# KeeWatch_LCD.net
KiCad netlist of a schematic drawn in Altium Designer
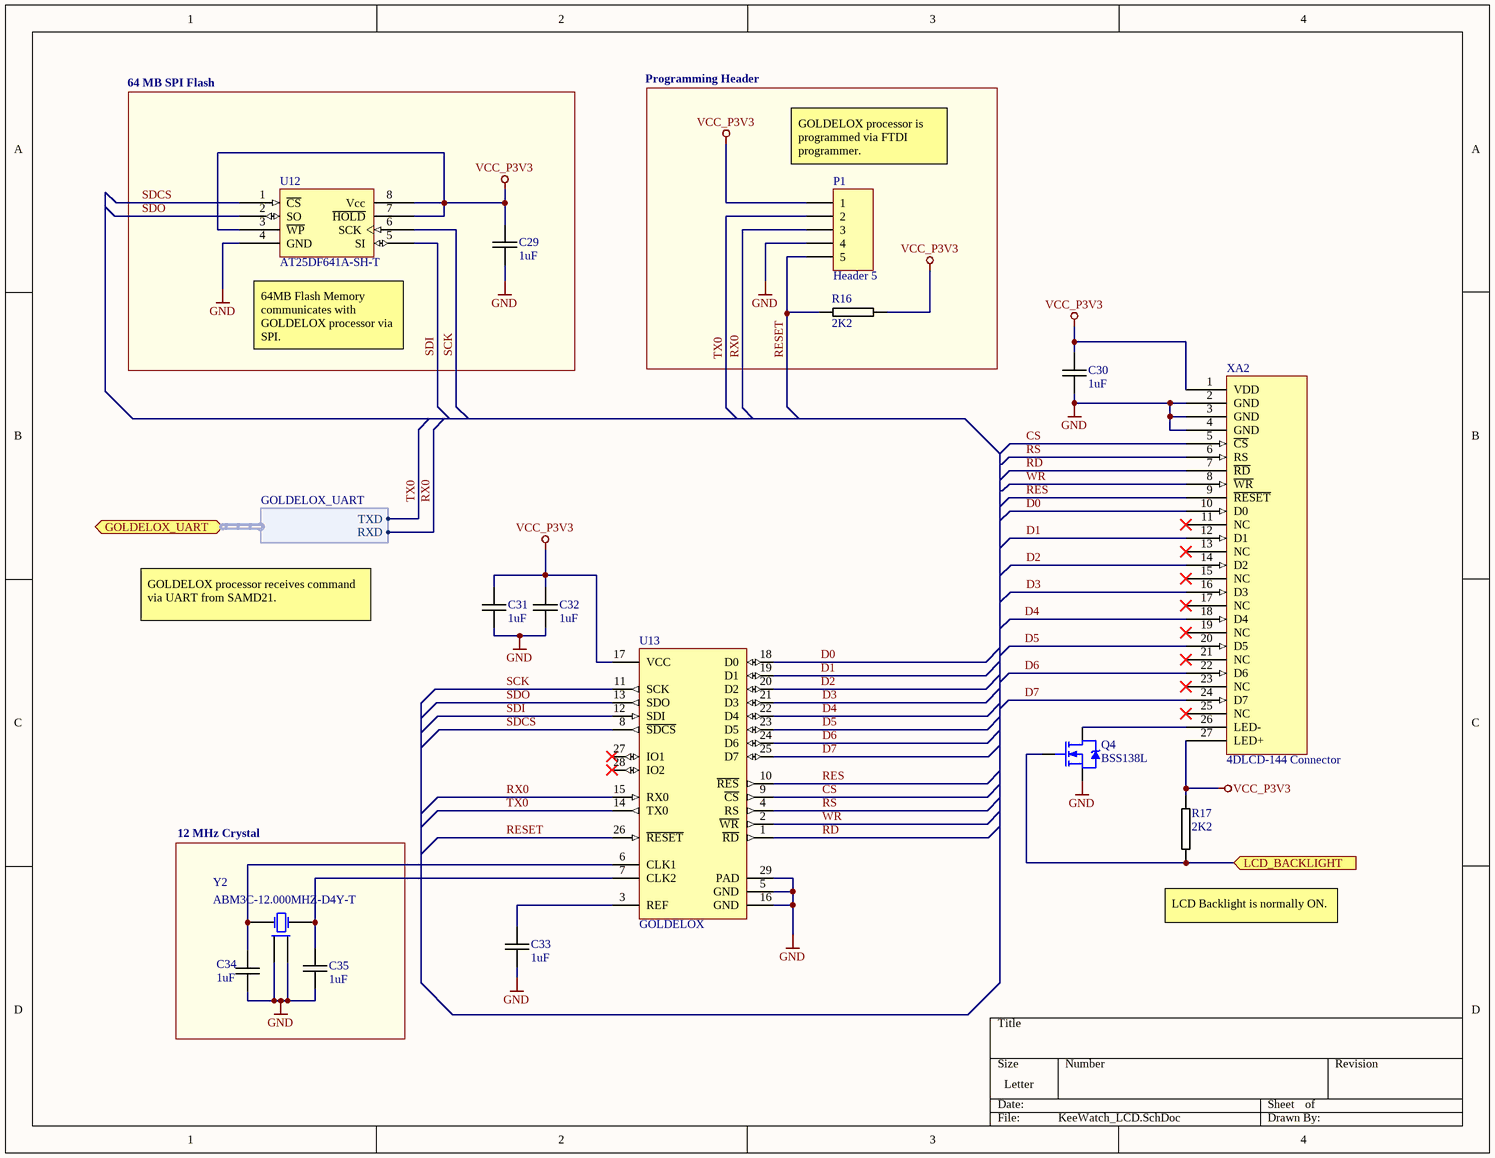
[diagram p0: KeeWatch_LCD.SchDoc]

(export (version "E")
  (design (tool "Eeschema 10.0.6"))
  (components
    (comp (ref "C29")
      (value "1uF")
      (footprint "0603-Cap")
      (description "CAPACITOR 0603 CERAMIC")
      (libsource (lib "Passives") (part "0603-Cap"))
    )
    (comp (ref "C30")
      (value "1uF")
      (footprint "0603-Cap")
      (description "CAPACITOR 0603 CERAMIC")
      (libsource (lib "Passives") (part "0603-Cap"))
    )
    (comp (ref "C31")
      (value "1uF")
      (footprint "0603-Cap")
      (description "CAPACITOR 0603 CERAMIC")
      (libsource (lib "Passives") (part "0603-Cap"))
    )
    (comp (ref "C32")
      (value "1uF")
      (footprint "0603-Cap")
      (description "CAPACITOR 0603 CERAMIC")
      (libsource (lib "Passives") (part "0603-Cap"))
    )
    (comp (ref "C33")
      (value "1uF")
      (footprint "0603-Cap")
      (description "CAPACITOR 0603 CERAMIC")
      (libsource (lib "Passives") (part "0603-Cap"))
    )
    (comp (ref "C34")
      (value "1uF")
      (footprint "0603-Cap")
      (description "CAPACITOR 0603 CERAMIC")
      (libsource (lib "Passives") (part "0603-Cap"))
    )
    (comp (ref "C35")
      (value "1uF")
      (footprint "0603-Cap")
      (description "CAPACITOR 0603 CERAMIC")
      (libsource (lib "Passives") (part "0603-Cap"))
    )
    (comp (ref "P1")
      (value "Header 5")
      (footprint "1x5 header")
      (description "Header, 5-Pin")
      (fields (field (name "PUBLISHER") "Altium Limited"))
      (libsource (lib "Miscellaneous Connectors") (part "Header 5"))
    )
    (comp (ref "Q4") (value "BSS138L") (footprint "SOT23-GDS") (libsource (lib "WATCH") (part "BSS138L")))
    (comp (ref "R16")
      (value "2K2")
      (footprint "0603-RES")
      (description "GENERIC RESISTOR 0603")
      (libsource (lib "Passives") (part "0603-Res"))
    )
    (comp (ref "R17")
      (value "2K2")
      (footprint "0603-RES")
      (description "GENERIC RESISTOR 0603")
      (libsource (lib "Passives") (part "0603-Res"))
    )
    (comp (ref "U12")
      (value "AT25DF641A-SH-T")
      (footprint "SO8_N")
      (description "64-Mbit, 2.7V Minimum SPI Serial Flash Memory with Dual–I/O Support")
      (libsource (lib "WATCH") (part "AT25DF641A-SH-T"))
    )
    (comp (ref "U13")
      (value "GOLDELOX")
      (footprint "4DS-QFN-3700X3700-28_V")
      (fields (field (name "MANUFACTURER") "4D Systems"))
      (libsource (lib "WATCH") (part "GOLDELOX"))
    )
    (comp (ref "XA2")
      (value "4DLCD-144 Connector")
      (footprint "4DLCD-144 27-pin Connector")
      (description "4DLCD-144 27-pin Flex Connector")
      (libsource (lib "WATCH") (part "4DLCD-144 Connector"))
    )
    (comp (ref "Y2")
      (value "ABM3C-12.000MHZ-D4Y-T")
      (footprint "CRYSTAL")
      (description "CERAMIC SMD CRYSTAL")
      (libsource (lib "Schlib2") (part "ABM3C-12.000MHZ-D4Y-T"))
    )
  )
  (nets
    (net (code "2") (name "/CS") (class "Default")
      (node (ref "U13") (pin "9") (pinfunction "~{CS}_9") (pintype "output"))
      (node (ref "XA2") (pin "5") (pinfunction "~{CS}_5") (pintype "input"))
    )
    (net (code "3") (name "/D0") (class "Default")
      (node (ref "U13") (pin "18") (pinfunction "D0_18") (pintype "bidirectional"))
      (node (ref "XA2") (pin "10") (pinfunction "D0_10") (pintype "input"))
    )
    (net (code "4") (name "/D1") (class "Default")
      (node (ref "U13") (pin "19") (pinfunction "D1_19") (pintype "bidirectional"))
      (node (ref "XA2") (pin "12") (pinfunction "D1_12") (pintype "input"))
    )
    (net (code "5") (name "/D2") (class "Default")
      (node (ref "U13") (pin "20") (pinfunction "D2_20") (pintype "bidirectional"))
      (node (ref "XA2") (pin "14") (pinfunction "D2_14") (pintype "input"))
    )
    (net (code "6") (name "/D3") (class "Default")
      (node (ref "U13") (pin "21") (pinfunction "D3_21") (pintype "bidirectional"))
      (node (ref "XA2") (pin "16") (pinfunction "D3_16") (pintype "input"))
    )
    (net (code "7") (name "/D4") (class "Default")
      (node (ref "U13") (pin "22") (pinfunction "D4_22") (pintype "bidirectional"))
      (node (ref "XA2") (pin "18") (pinfunction "D4_18") (pintype "input"))
    )
    (net (code "8") (name "/D5") (class "Default")
      (node (ref "U13") (pin "23") (pinfunction "D5_23") (pintype "bidirectional"))
      (node (ref "XA2") (pin "20") (pinfunction "D5_20") (pintype "input"))
    )
    (net (code "9") (name "/D6") (class "Default")
      (node (ref "U13") (pin "24") (pinfunction "D6_24") (pintype "bidirectional"))
      (node (ref "XA2") (pin "22") (pinfunction "D6_22") (pintype "input"))
    )
    (net (code "10") (name "/D7") (class "Default")
      (node (ref "U13") (pin "25") (pinfunction "D7_25") (pintype "bidirectional"))
      (node (ref "XA2") (pin "24") (pinfunction "D7_24") (pintype "input"))
    )
    (net (code "11") (name "/LCD_BACKLIGHT") (class "Default")
      (node (ref "Q4") (pin "1") (pinfunction "G_1") (pintype "passive"))
      (node (ref "R17") (pin "2") (pintype "passive"))
    )
    (net (code "12") (name "/RD") (class "Default")
      (node (ref "U13") (pin "1") (pinfunction "~{RD}_1") (pintype "output"))
      (node (ref "XA2") (pin "7") (pinfunction "~{RD}_7") (pintype "passive"))
    )
    (net (code "13") (name "/RES") (class "Default")
      (node (ref "U13") (pin "10") (pinfunction "~{RES}_10") (pintype "output"))
      (node (ref "XA2") (pin "9") (pinfunction "~{RESET}_9") (pintype "passive"))
    )
    (net (code "14") (name "/RESET") (class "Default")
      (node (ref "P1") (pin "5") (pinfunction "5_5") (pintype "passive"))
      (node (ref "R16") (pin "1") (pintype "passive"))
      (node (ref "U13") (pin "26") (pinfunction "~{RESET}_26") (pintype "input"))
    )
    (net (code "15") (name "/RS") (class "Default")
      (node (ref "U13") (pin "4") (pinfunction "RS_4") (pintype "output"))
      (node (ref "XA2") (pin "6") (pinfunction "RS_6") (pintype "input"))
    )
    (net (code "16") (name "/RX0") (class "Default")
      (node (ref "P1") (pin "3") (pinfunction "3_3") (pintype "passive"))
      (node (ref "U13") (pin "15") (pinfunction "RX0_15") (pintype "input"))
    )
    (net (code "17") (name "/SCK") (class "Default")
      (node (ref "U12") (pin "6") (pinfunction "SCK_6") (pintype "input"))
      (node (ref "U13") (pin "11") (pinfunction "SCK_11") (pintype "output"))
    )
    (net (code "18") (name "/SDCS") (class "Default")
      (node (ref "U12") (pin "1") (pinfunction "~{CS}_1") (pintype "input"))
      (node (ref "U13") (pin "8") (pinfunction "~{SDCS}_8") (pintype "output"))
    )
    (net (code "19") (name "/SDI") (class "Default")
      (node (ref "U12") (pin "5") (pinfunction "SI_5") (pintype "bidirectional"))
      (node (ref "U13") (pin "12") (pinfunction "SDI_12") (pintype "input"))
    )
    (net (code "20") (name "/SDO") (class "Default")
      (node (ref "U12") (pin "2") (pinfunction "SO_2") (pintype "bidirectional"))
      (node (ref "U13") (pin "13") (pinfunction "SDO_13") (pintype "output"))
    )
    (net (code "21") (name "/TX0") (class "Default")
      (node (ref "P1") (pin "2") (pinfunction "2_2") (pintype "passive"))
      (node (ref "U13") (pin "14") (pinfunction "TX0_14") (pintype "output"))
    )
    (net (code "22") (name "/WR") (class "Default")
      (node (ref "U13") (pin "2") (pinfunction "~{WR}_2") (pintype "output"))
      (node (ref "XA2") (pin "8") (pinfunction "~{WR}_8") (pintype "input"))
    )
    (net (code "24") (name "GND") (class "Default")
      (node (ref "C29") (pin "2") (pintype "passive"))
      (node (ref "C30") (pin "2") (pintype "passive"))
      (node (ref "C31") (pin "2") (pintype "passive"))
      (node (ref "C32") (pin "2") (pintype "passive"))
      (node (ref "C33") (pin "2") (pintype "passive"))
      (node (ref "C34") (pin "2") (pintype "passive"))
      (node (ref "C35") (pin "2") (pintype "passive"))
      (node (ref "P1") (pin "4") (pinfunction "4_4") (pintype "passive"))
      (node (ref "Q4") (pin "3") (pinfunction "S_3") (pintype "passive"))
      (node (ref "U12") (pin "4") (pinfunction "GND_4") (pintype "passive"))
      (node (ref "U13") (pin "16") (pinfunction "GND_16") (pintype "power_in"))
      (node (ref "U13") (pin "29") (pinfunction "PAD_29") (pintype "power_in"))
      (node (ref "U13") (pin "5") (pinfunction "GND_5") (pintype "power_in"))
      (node (ref "XA2") (pin "2") (pinfunction "GND_2") (pintype "passive"))
      (node (ref "XA2") (pin "3") (pinfunction "GND_3") (pintype "passive"))
      (node (ref "XA2") (pin "4") (pinfunction "GND_4") (pintype "passive"))
      (node (ref "Y2") (pin "3") (pinfunction "GND_3") (pintype "passive"))
      (node (ref "Y2") (pin "4") (pinfunction "GND_4") (pintype "passive"))
    )
    (net (code "25") (name "Net-(Q4-D)") (class "Default")
      (node (ref "Q4") (pin "2") (pinfunction "D_2") (pintype "passive"))
      (node (ref "XA2") (pin "26") (pinfunction "LED-_26") (pintype "power_in"))
    )
    (net (code "26") (name "Net-(U13-CLK1)") (class "Default")
      (node (ref "C34") (pin "1") (pintype "passive"))
      (node (ref "U13") (pin "6") (pinfunction "CLK1_6") (pintype "passive"))
      (node (ref "Y2") (pin "1") (pinfunction "OSC1_1") (pintype "passive"))
    )
    (net (code "27") (name "Net-(U13-CLK2)") (class "Default")
      (node (ref "C35") (pin "1") (pintype "passive"))
      (node (ref "U13") (pin "7") (pinfunction "CLK2_7") (pintype "passive"))
      (node (ref "Y2") (pin "2") (pinfunction "OSC2_2") (pintype "passive"))
    )
    (net (code "28") (name "Net-(U13-REF)") (class "Default")
      (node (ref "C33") (pin "1") (pintype "passive"))
      (node (ref "U13") (pin "3") (pinfunction "REF_3") (pintype "passive"))
    )
    (net (code "29") (name "VCC_P3V3") (class "Default")
      (node (ref "C29") (pin "1") (pintype "passive"))
      (node (ref "C30") (pin "1") (pintype "passive"))
      (node (ref "C31") (pin "1") (pintype "passive"))
      (node (ref "C32") (pin "1") (pintype "passive"))
      (node (ref "P1") (pin "1") (pinfunction "1_1") (pintype "passive"))
      (node (ref "R16") (pin "2") (pintype "passive"))
      (node (ref "R17") (pin "1") (pintype "passive"))
      (node (ref "U12") (pin "3") (pinfunction "~{WP}_3") (pintype "passive"))
      (node (ref "U12") (pin "7") (pinfunction "~{HOLD}_7") (pintype "passive"))
      (node (ref "U12") (pin "8") (pinfunction "Vcc_8") (pintype "power_in"))
      (node (ref "U13") (pin "17") (pinfunction "VCC_17") (pintype "power_in"))
      (node (ref "XA2") (pin "1") (pinfunction "VDD_1") (pintype "power_in"))
      (node (ref "XA2") (pin "27") (pinfunction "LED+_27") (pintype "power_in"))
    )
    (net (code "30") (name "unconnected-(U13-IO1-Pad27)") (class "Default")
      (node (ref "U13") (pin "27") (pinfunction "IO1_27") (pintype "bidirectional+no_connect"))
    )
    (net (code "31") (name "unconnected-(U13-IO2-Pad28)") (class "Default")
      (node (ref "U13") (pin "28") (pinfunction "IO2_28") (pintype "bidirectional+no_connect"))
    )
    (net (code "32") (name "unconnected-(XA2-NC-Pad11)") (class "Default")
      (node (ref "XA2") (pin "11") (pinfunction "NC_11") (pintype "passive+no_connect"))
    )
    (net (code "33") (name "unconnected-(XA2-NC-Pad13)") (class "Default")
      (node (ref "XA2") (pin "13") (pinfunction "NC_13") (pintype "passive+no_connect"))
    )
    (net (code "34") (name "unconnected-(XA2-NC-Pad15)") (class "Default")
      (node (ref "XA2") (pin "15") (pinfunction "NC_15") (pintype "passive+no_connect"))
    )
    (net (code "35") (name "unconnected-(XA2-NC-Pad17)") (class "Default")
      (node (ref "XA2") (pin "17") (pinfunction "NC_17") (pintype "passive+no_connect"))
    )
    (net (code "36") (name "unconnected-(XA2-NC-Pad19)") (class "Default")
      (node (ref "XA2") (pin "19") (pinfunction "NC_19") (pintype "passive+no_connect"))
    )
    (net (code "37") (name "unconnected-(XA2-NC-Pad21)") (class "Default")
      (node (ref "XA2") (pin "21") (pinfunction "NC_21") (pintype "passive+no_connect"))
    )
    (net (code "38") (name "unconnected-(XA2-NC-Pad23)") (class "Default")
      (node (ref "XA2") (pin "23") (pinfunction "NC_23") (pintype "passive+no_connect"))
    )
    (net (code "39") (name "unconnected-(XA2-NC-Pad25)") (class "Default")
      (node (ref "XA2") (pin "25") (pinfunction "NC_25") (pintype "passive+no_connect"))
    )
  )
)
